# Sheet1_WATERALARM.net
KiCad netlist of a schematic drawn in Altium Designer
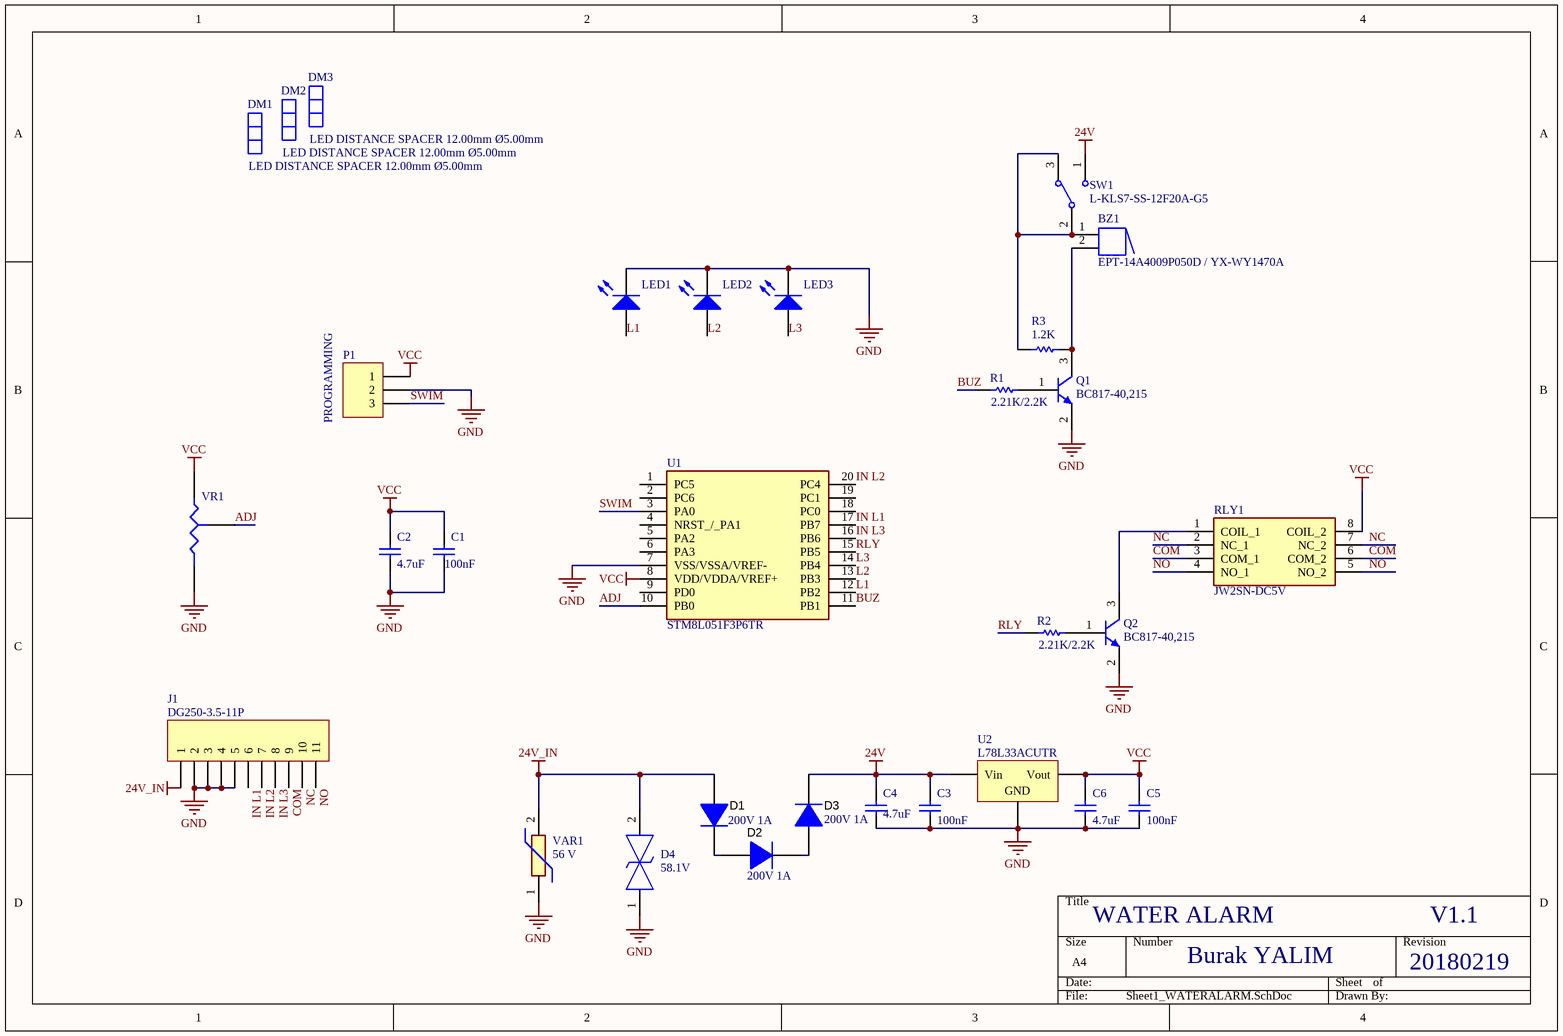
[diagram p0: Sheet1_WATERALARM.SchDoc]

(export (version "E")
  (design (tool "Eeschema 10.0.6"))
  (components
    (comp (ref "BZ1")
      (value "EPT-14A4009P050D / YX-WY1470A")
      (footprint "piezo buzzer")
      (description "BUZZER PIEZO W/O CIRCUIT 9V 4-KHZ THT")
      (fields (field (name "MANUFACTURER") "SANCO / YXDZ"))
      (libsource (lib "Miscellaneous Devices") (part "Buzzer"))
    )
    (comp (ref "C1")
      (value "100nF")
      (footprint "C0805-N")
      (description "MLCC (2012) 0805 100nF 50VDC ±10% X7R")
      (fields
        (field (name "MANUFACTURER") "SAMSUNG")
        (field (name "MANUFACTURER PART NUMBER") "CL21B104KBCNNNL")
      )
      (libsource (lib "Miscellaneous Devices") (part "Cap"))
    )
    (comp (ref "C2")
      (value "4.7uF")
      (footprint "C0805-N")
      (description "MLCC (2012) 0805 4.7uF 50VDC ±10% X5R")
      (fields
        (field (name "MANUFACTURER") "SAMSUNG")
        (field (name "MANUFACTURER PART NUMBER") "CL21A475KBQNNNE")
      )
      (libsource (lib "Miscellaneous Devices") (part "Cap"))
    )
    (comp (ref "C3")
      (value "100nF")
      (footprint "C0805-N")
      (description "MLCC (2012) 0805 100nF 50VDC ±10% X7R")
      (fields
        (field (name "MANUFACTURER") "SAMSUNG")
        (field (name "MANUFACTURER PART NUMBER") "CL21B104KBCNNNL")
      )
      (libsource (lib "Miscellaneous Devices") (part "Cap"))
    )
    (comp (ref "C4")
      (value "4.7uF")
      (footprint "C0805-N")
      (description "MLCC (2012) 0805 4.7uF 50VDC ±10% X5R")
      (fields
        (field (name "MANUFACTURER") "SAMSUNG")
        (field (name "MANUFACTURER PART NUMBER") "CL21A475KBQNNNE")
      )
      (libsource (lib "Miscellaneous Devices") (part "Cap"))
    )
    (comp (ref "C5")
      (value "100nF")
      (footprint "C0805-N")
      (description "MLCC (2012) 0805 100nF 50VDC ±10% X7R")
      (fields
        (field (name "MANUFACTURER") "SAMSUNG")
        (field (name "MANUFACTURER PART NUMBER") "CL21B104KBCNNNL")
      )
      (libsource (lib "Miscellaneous Devices") (part "Cap"))
    )
    (comp (ref "C6")
      (value "4.7uF")
      (footprint "C0805-N")
      (description "MLCC (2012) 0805 4.7uF 50VDC ±10% X5R")
      (fields
        (field (name "MANUFACTURER") "SAMSUNG")
        (field (name "MANUFACTURER PART NUMBER") "CL21A475KBQNNNE")
      )
      (libsource (lib "Miscellaneous Devices") (part "Cap"))
    )
    (comp (ref "D1")
      (value "200V 1A")
      (footprint "SMA")
      (description "DIODE U.FAST SINGLE 1A 200V DO214AC (SMA) SMT")
      (fields
        (field (name "MANUFACTURER PART NUMBER") "US1D_R1_00001 / US1D-SMA-MDD")
        (field (name "MANUFACTURER") "ON Semiconductor /  MDD(Microdiode Semiconductor)")
      )
      (libsource (lib "PMP30720_RevA") (part "MURA160T3G"))
    )
    (comp (ref "D2")
      (value "200V 1A")
      (footprint "SMA")
      (description "DIODE U.FAST SINGLE 1A 200V DO214AC (SMA) SMT")
      (fields
        (field (name "MANUFACTURER PART NUMBER") "US1D_R1_00001 / US1D-SMA-MDD")
        (field (name "MANUFACTURER") "ON Semiconductor /  MDD(Microdiode Semiconductor)")
      )
      (libsource (lib "PMP30720_RevA") (part "MURA160T3G"))
    )
    (comp (ref "D3")
      (value "200V 1A")
      (footprint "SMA")
      (description "DIODE U.FAST SINGLE 1A 200V DO214AC (SMA) SMT")
      (fields
        (field (name "MANUFACTURER PART NUMBER") "US1D_R1_00001 / US1D-SMA-MDD")
        (field (name "MANUFACTURER") "ON Semiconductor /  MDD(Microdiode Semiconductor)")
      )
      (libsource (lib "PMP30720_RevA") (part "MURA160T3G"))
    )
    (comp (ref "D4")
      (value "58.1V")
      (footprint "SamacSys:DIONM5127X250N")
      (description "58.1V Clamp 6.9A Ipp Tvs Diode Surface Mount DO-214AC (SMA)")
      (fields
        (field (name "MANUFACTURER") "YAGEO / MDD(Microdiode Semiconductor)")
        (field (name "MANUFACTURER PART NUMBER") "SMAJ36CA/TR7 / SMAJ36CA-UMW")
      )
      (libsource (lib "*") (part "SMAJ36CA-AT_TR7"))
    )
    (comp (ref "DM1")
      (value "LED DISTANCE SPACER 12.00mm Ø5.00mm")
      (description "LED DISTANCE SPACER 12.00mm NONE Ø5.00mm")
      (fields
        (field (name "MANUFACTURER") "KLS ELECTRONIC")
        (field (name "MANUFACTURER PART NUMBER") "L-KLS8-0108-LED-12")
      )
      (libsource (lib "GentekConnectorLib") (part "DISTANCE 11MM M3"))
    )
    (comp (ref "DM2")
      (value "LED DISTANCE SPACER 12.00mm Ø5.00mm")
      (description "LED DISTANCE SPACER 12.00mm NONE Ø5.00mm")
      (fields
        (field (name "MANUFACTURER") "KLS ELECTRONIC")
        (field (name "MANUFACTURER PART NUMBER") "L-KLS8-0108-LED-12")
      )
      (libsource (lib "GentekConnectorLib") (part "DISTANCE 11MM M3"))
    )
    (comp (ref "DM3")
      (value "LED DISTANCE SPACER 12.00mm Ø5.00mm")
      (description "LED DISTANCE SPACER 12.00mm NONE Ø5.00mm")
      (fields
        (field (name "MANUFACTURER") "KLS ELECTRONIC")
        (field (name "MANUFACTURER PART NUMBER") "L-KLS8-0108-LED-12")
      )
      (libsource (lib "GentekConnectorLib") (part "DISTANCE 11MM M3"))
    )
    (comp (ref "J1")
      (value "DG250-3.5-11P")
      (footprint "11 pin Terminal sping loaded")
      (description "TERM.BLK.3.50MM 11P PCB TYPE GRAY GAOSONG")
      (fields (field (name "MANUFACTURER") "DEGSON/GAOSONG"))
      (libsource (lib "WATERALARM_V1.1") (part "DG250-3.5-11P"))
    )
    (comp (ref "LED1")
      (value "3R4HD-7-TB")
      (footprint "led 3mm")
      (description "LED 3MM RED 30mcd 35° RED/DIFFUSED")
      (fields (field (name "MANUFACTURER") "STRONG BASE"))
      (libsource (lib "Miscellaneous Devices") (part "LED2"))
    )
    (comp (ref "LED2")
      (value "3R4HD-7-TB")
      (footprint "led 3mm")
      (description "LED 3MM RED 30mcd 35° RED/DIFFUSED")
      (fields (field (name "MANUFACTURER") "STRONG BASE"))
      (libsource (lib "Miscellaneous Devices") (part "LED2"))
    )
    (comp (ref "LED3")
      (value "3R4HD-7-TB")
      (footprint "led 3mm")
      (description "LED 3MM RED 30mcd 35° RED/DIFFUSED")
      (fields (field (name "MANUFACTURER") "STRONG BASE"))
      (libsource (lib "Miscellaneous Devices") (part "LED2"))
    )
    (comp (ref "P1")
      (value "PROGRAMMING")
      (footprint "HDR1X3")
      (description "Header, 3-Pin")
      (libsource (lib "Miscellaneous Connectors") (part "Header 3"))
    )
    (comp (ref "Q1")
      (value "BC817-40,215")
      (footprint "SOT-23")
      (description "TRANSISTOR DIS.500mA 45V NPN SOT23 GEN. SMT")
      (fields (field (name "MANUFACTURER") "NXP"))
      (libsource (lib "Miscellaneous Devices") (part "NPN"))
    )
    (comp (ref "Q2")
      (value "BC817-40,215")
      (footprint "SOT-23")
      (description "TRANSISTOR DIS.500mA 45V NPN SOT23 GEN. SMT")
      (fields (field (name "MANUFACTURER") "NXP"))
      (libsource (lib "Miscellaneous Devices") (part "NPN"))
    )
    (comp (ref "R1")
      (value "2.21K/2.2K")
      (footprint "C0805-N")
      (description "RES.(2012) 0805 2.21K/2.2K Ohms 1%/5% 1/8W-S 100PPM")
      (fields
        (field (name "MANUFACTURER") "ROYALOHM")
        (field (name "MANUFACTURER PART NUMBER") "0805S8F2211T5E/0805S8J0222T5E")
      )
      (libsource (lib "Miscellaneous Devices") (part "Res1"))
    )
    (comp (ref "R2")
      (value "2.21K/2.2K")
      (footprint "C0805-N")
      (description "RES.(2012) 0805 2.21K/2.2K Ohms 1%/5% 1/8W-S 100PPM")
      (fields
        (field (name "MANUFACTURER") "ROYALOHM")
        (field (name "MANUFACTURER PART NUMBER") "0805S8F2211T5E/0805S8J0222T5E")
      )
      (libsource (lib "Miscellaneous Devices") (part "Res1"))
    )
    (comp (ref "R3")
      (value "1.2K")
      (footprint "C1210")
      (description "RES.(3225) 1210 1.2K Ohms 5% 1/2W 200PPM")
      (fields
        (field (name "MANUFACTURER") "HOTTECH")
        (field (name "MANUFACTURER PART NUMBER") "RI1210L122JT")
      )
      (libsource (lib "Miscellaneous Devices") (part "Res1"))
    )
    (comp (ref "RLY1")
      (value "JW2SN-DC5V")
      (footprint "SamacSys:JW2SNDC5V")
      (description "General Purpose Relay DPDT (2 Form C) 5VDC Coil Through Hole")
      (fields (field (name "MANUFACTURER") "Panasonic"))
      (libsource (lib "*") (part "JW2SN-DC5V"))
    )
    (comp (ref "SW1")
      (value "L-KLS7-SS-12F20A-G5")
      (footprint "Slide Switch")
      (description "SWITCH SLIDE 1P2T 500mA 50V On-On THT V/T")
      (fields (field (name "MANUFACTURER") "KLS ELECTRONIC"))
      (libsource (lib "Miscellaneous Devices") (part "SW-SPDT"))
    )
    (comp (ref "U1")
      (value "STM8L051F3P6TR")
      (footprint "SamacSys:SOP65P640X120-20N")
      (description "IC-8L051 MCU 8BIT 8K FLASH TSSOP20")
      (fields
        (field (name "MANUFACTURER") "STMicroelectronics")
        (field (name "MOUSER PART NUMBER") "511-STM8L051F3P6TR")
      )
      (libsource (lib "*") (part "STM8L051F3P6TR"))
    )
    (comp (ref "U2")
      (value "L78L33ACUTR")
      (footprint "SOT89M")
      (description "IC-78L33 VOLTAGE REGULATOR 3.3V 100mA SOT89 ST")
      (fields (field (name "MANUFACTURER") "STM"))
      (libsource (lib "Miscellaneous Devices") (part "Volt Reg"))
    )
    (comp (ref "VAR1")
      (value "TVR07470KSY")
      (footprint "SamacSys:ERZV05D180")
      (description "VARISTOR DISC 7MM 47V 250A 30VAC 38VDC THT")
      (fields (field (name "VARISTOR VOLTAGE") "56 V") (field (name "MANUFACTURER") "THINKING"))
      (libsource (lib "*") (part "ERZ-V05D180"))
    )
    (comp (ref "VR1")
      (value "L-KLS4-WH06-2A-103")
      (footprint "Potentiometer")
      (description "TRIMPOT CARBON V 6MM 10K")
      (fields (field (name "MANUFACTURER") "KLS ELECTRONIC"))
      (libsource (lib "Miscellaneous Devices") (part "Res Tap"))
    )
  )
  (nets
    (net (code "1") (name "/ADJ") (class "Default")
      (node (ref "U1") (pin "10") (pinfunction "PB0_10") (pintype "passive"))
      (node (ref "VR1") (pin "3") (pinfunction "TAP_3") (pintype "passive"))
    )
    (net (code "2") (name "/BUZ") (class "Default")
      (node (ref "R1") (pin "2") (pinfunction "2_2") (pintype "passive"))
      (node (ref "U1") (pin "11") (pinfunction "PB1_11") (pintype "passive"))
    )
    (net (code "3") (name "/COM") (class "Default")
      (node (ref "J1") (pin "9") (pinfunction "9_9") (pintype "passive"))
      (node (ref "RLY1") (pin "3") (pinfunction "COM_1_3") (pintype "passive"))
      (node (ref "RLY1") (pin "6") (pinfunction "COM_2_6") (pintype "passive"))
    )
    (net (code "4") (name "/IN L1") (class "Default")
      (node (ref "J1") (pin "6") (pinfunction "6_6") (pintype "passive"))
      (node (ref "U1") (pin "17") (pinfunction "PB7_17") (pintype "passive"))
    )
    (net (code "5") (name "/IN L2") (class "Default")
      (node (ref "J1") (pin "7") (pinfunction "7_7") (pintype "passive"))
      (node (ref "U1") (pin "20") (pinfunction "PC4_20") (pintype "passive"))
    )
    (net (code "6") (name "/IN L3") (class "Default")
      (node (ref "J1") (pin "8") (pinfunction "8_8") (pintype "passive"))
      (node (ref "U1") (pin "16") (pinfunction "PB6_16") (pintype "passive"))
    )
    (net (code "7") (name "/L1") (class "Default")
      (node (ref "LED1") (pin "1") (pinfunction "A_1") (pintype "passive"))
      (node (ref "U1") (pin "12") (pinfunction "PB2_12") (pintype "passive"))
    )
    (net (code "8") (name "/L2") (class "Default")
      (node (ref "LED2") (pin "1") (pinfunction "A_1") (pintype "passive"))
      (node (ref "U1") (pin "13") (pinfunction "PB3_13") (pintype "passive"))
    )
    (net (code "9") (name "/L3") (class "Default")
      (node (ref "LED3") (pin "1") (pinfunction "A_1") (pintype "passive"))
      (node (ref "U1") (pin "14") (pinfunction "PB4_14") (pintype "passive"))
    )
    (net (code "10") (name "/NC") (class "Default")
      (node (ref "J1") (pin "10") (pinfunction "10_10") (pintype "passive"))
      (node (ref "RLY1") (pin "2") (pinfunction "NC_1_2") (pintype "passive"))
      (node (ref "RLY1") (pin "7") (pinfunction "NC_2_7") (pintype "passive"))
    )
    (net (code "11") (name "/NO") (class "Default")
      (node (ref "J1") (pin "11") (pinfunction "11_11") (pintype "passive"))
      (node (ref "RLY1") (pin "4") (pinfunction "NO_1_4") (pintype "passive"))
      (node (ref "RLY1") (pin "5") (pinfunction "NO_2_5") (pintype "passive"))
    )
    (net (code "12") (name "/RLY") (class "Default")
      (node (ref "R2") (pin "2") (pinfunction "2_2") (pintype "passive"))
      (node (ref "U1") (pin "15") (pinfunction "PB5_15") (pintype "passive"))
    )
    (net (code "13") (name "/SWIM") (class "Default")
      (node (ref "P1") (pin "3") (pinfunction "3_3") (pintype "passive"))
      (node (ref "U1") (pin "3") (pinfunction "PA0_3") (pintype "passive"))
    )
    (net (code "14") (name "24V") (class "Default")
      (node (ref "C3") (pin "2") (pinfunction "2_2") (pintype "passive"))
      (node (ref "C4") (pin "2") (pinfunction "2_2") (pintype "passive"))
      (node (ref "D3") (pin "1") (pinfunction "K_1") (pintype "passive"))
      (node (ref "SW1") (pin "1") (pinfunction "1_1") (pintype "passive"))
      (node (ref "U2") (pin "1") (pinfunction "Vin_1") (pintype "passive"))
    )
    (net (code "15") (name "24V_IN") (class "Default")
      (node (ref "D1") (pin "2") (pinfunction "A_2") (pintype "passive"))
      (node (ref "D4") (pin "2") (pinfunction "2_2") (pintype "passive"))
      (node (ref "J1") (pin "1") (pinfunction "1_1") (pintype "passive"))
      (node (ref "VAR1") (pin "2") (pinfunction "2_2") (pintype "passive"))
    )
    (net (code "16") (name "GND") (class "Default")
      (node (ref "C1") (pin "1") (pinfunction "1_1") (pintype "passive"))
      (node (ref "C2") (pin "1") (pinfunction "1_1") (pintype "passive"))
      (node (ref "C3") (pin "1") (pinfunction "1_1") (pintype "passive"))
      (node (ref "C4") (pin "1") (pinfunction "1_1") (pintype "passive"))
      (node (ref "C5") (pin "1") (pinfunction "1_1") (pintype "passive"))
      (node (ref "C6") (pin "1") (pinfunction "1_1") (pintype "passive"))
      (node (ref "D4") (pin "1") (pinfunction "1_1") (pintype "passive"))
      (node (ref "J1") (pin "2") (pinfunction "2_2") (pintype "passive"))
      (node (ref "J1") (pin "3") (pinfunction "3_3") (pintype "passive"))
      (node (ref "J1") (pin "4") (pinfunction "4_4") (pintype "passive"))
      (node (ref "J1") (pin "5") (pinfunction "5_5") (pintype "passive"))
      (node (ref "LED1") (pin "2") (pinfunction "K_2") (pintype "passive"))
      (node (ref "LED2") (pin "2") (pinfunction "K_2") (pintype "passive"))
      (node (ref "LED3") (pin "2") (pinfunction "K_2") (pintype "passive"))
      (node (ref "P1") (pin "2") (pinfunction "2_2") (pintype "passive"))
      (node (ref "Q1") (pin "2") (pinfunction "E_2") (pintype "passive"))
      (node (ref "Q2") (pin "2") (pinfunction "E_2") (pintype "passive"))
      (node (ref "U1") (pin "7") (pinfunction "VSS/VSSA/VREF-_7") (pintype "passive"))
      (node (ref "U2") (pin "2") (pinfunction "GND_2") (pintype "passive"))
      (node (ref "VAR1") (pin "1") (pinfunction "1_1") (pintype "passive"))
      (node (ref "VR1") (pin "2") (pinfunction "B_2") (pintype "passive"))
    )
    (net (code "17") (name "Net-(BZ1-Pad1)") (class "Default")
      (node (ref "BZ1") (pin "1") (pinfunction "1_1") (pintype "passive"))
      (node (ref "R3") (pin "2") (pinfunction "2_2") (pintype "passive"))
      (node (ref "SW1") (pin "2") (pinfunction "2_2") (pintype "passive"))
      (node (ref "SW1") (pin "3") (pinfunction "3_3") (pintype "passive"))
    )
    (net (code "18") (name "Net-(D1-K)") (class "Default")
      (node (ref "D1") (pin "1") (pinfunction "K_1") (pintype "passive"))
      (node (ref "D2") (pin "2") (pinfunction "A_2") (pintype "passive"))
    )
    (net (code "19") (name "Net-(D2-K)") (class "Default")
      (node (ref "D2") (pin "1") (pinfunction "K_1") (pintype "passive"))
      (node (ref "D3") (pin "2") (pinfunction "A_2") (pintype "passive"))
    )
    (net (code "20") (name "Net-(Q1-B)") (class "Default")
      (node (ref "Q1") (pin "1") (pinfunction "B_1") (pintype "passive"))
      (node (ref "R1") (pin "1") (pinfunction "1_1") (pintype "passive"))
    )
    (net (code "21") (name "Net-(Q1-C)") (class "Default")
      (node (ref "BZ1") (pin "2") (pinfunction "2_2") (pintype "passive"))
      (node (ref "Q1") (pin "3") (pinfunction "C_3") (pintype "passive"))
      (node (ref "R3") (pin "1") (pinfunction "1_1") (pintype "passive"))
    )
    (net (code "22") (name "Net-(Q2-B)") (class "Default")
      (node (ref "Q2") (pin "1") (pinfunction "B_1") (pintype "passive"))
      (node (ref "R2") (pin "1") (pinfunction "1_1") (pintype "passive"))
    )
    (net (code "23") (name "Net-(Q2-C)") (class "Default")
      (node (ref "Q2") (pin "3") (pinfunction "C_3") (pintype "passive"))
      (node (ref "RLY1") (pin "1") (pinfunction "COIL_1_1") (pintype "passive"))
    )
    (net (code "24") (name "VCC") (class "Default")
      (node (ref "C1") (pin "2") (pinfunction "2_2") (pintype "passive"))
      (node (ref "C2") (pin "2") (pinfunction "2_2") (pintype "passive"))
      (node (ref "C5") (pin "2") (pinfunction "2_2") (pintype "passive"))
      (node (ref "C6") (pin "2") (pinfunction "2_2") (pintype "passive"))
      (node (ref "P1") (pin "1") (pinfunction "1_1") (pintype "passive"))
      (node (ref "RLY1") (pin "8") (pinfunction "COIL_2_8") (pintype "passive"))
      (node (ref "U1") (pin "8") (pinfunction "VDD/VDDA/VREF+_8") (pintype "passive"))
      (node (ref "U2") (pin "3") (pinfunction "Vout_3") (pintype "passive"))
      (node (ref "VR1") (pin "1") (pinfunction "A_1") (pintype "passive"))
    )
    (net (code "25") (name "unconnected-(U1-NRST_{slash}_PA1-Pad4)") (class "Default")
      (node (ref "U1") (pin "4") (pinfunction "NRST_/_PA1_4") (pintype "passive"))
    )
    (net (code "26") (name "unconnected-(U1-PA2-Pad5)") (class "Default")
      (node (ref "U1") (pin "5") (pinfunction "PA2_5") (pintype "passive"))
    )
    (net (code "27") (name "unconnected-(U1-PA3-Pad6)") (class "Default")
      (node (ref "U1") (pin "6") (pinfunction "PA3_6") (pintype "passive"))
    )
    (net (code "28") (name "unconnected-(U1-PC0-Pad18)") (class "Default")
      (node (ref "U1") (pin "18") (pinfunction "PC0_18") (pintype "passive"))
    )
    (net (code "29") (name "unconnected-(U1-PC1-Pad19)") (class "Default")
      (node (ref "U1") (pin "19") (pinfunction "PC1_19") (pintype "passive"))
    )
    (net (code "30") (name "unconnected-(U1-PC5-Pad1)") (class "Default")
      (node (ref "U1") (pin "1") (pinfunction "PC5_1") (pintype "passive"))
    )
    (net (code "31") (name "unconnected-(U1-PC6-Pad2)") (class "Default")
      (node (ref "U1") (pin "2") (pinfunction "PC6_2") (pintype "passive"))
    )
    (net (code "32") (name "unconnected-(U1-PD0-Pad9)") (class "Default")
      (node (ref "U1") (pin "9") (pinfunction "PD0_9") (pintype "passive"))
    )
  )
)
